# IoT_Pro_01.net
KiCad netlist of a schematic drawn in EAGLE
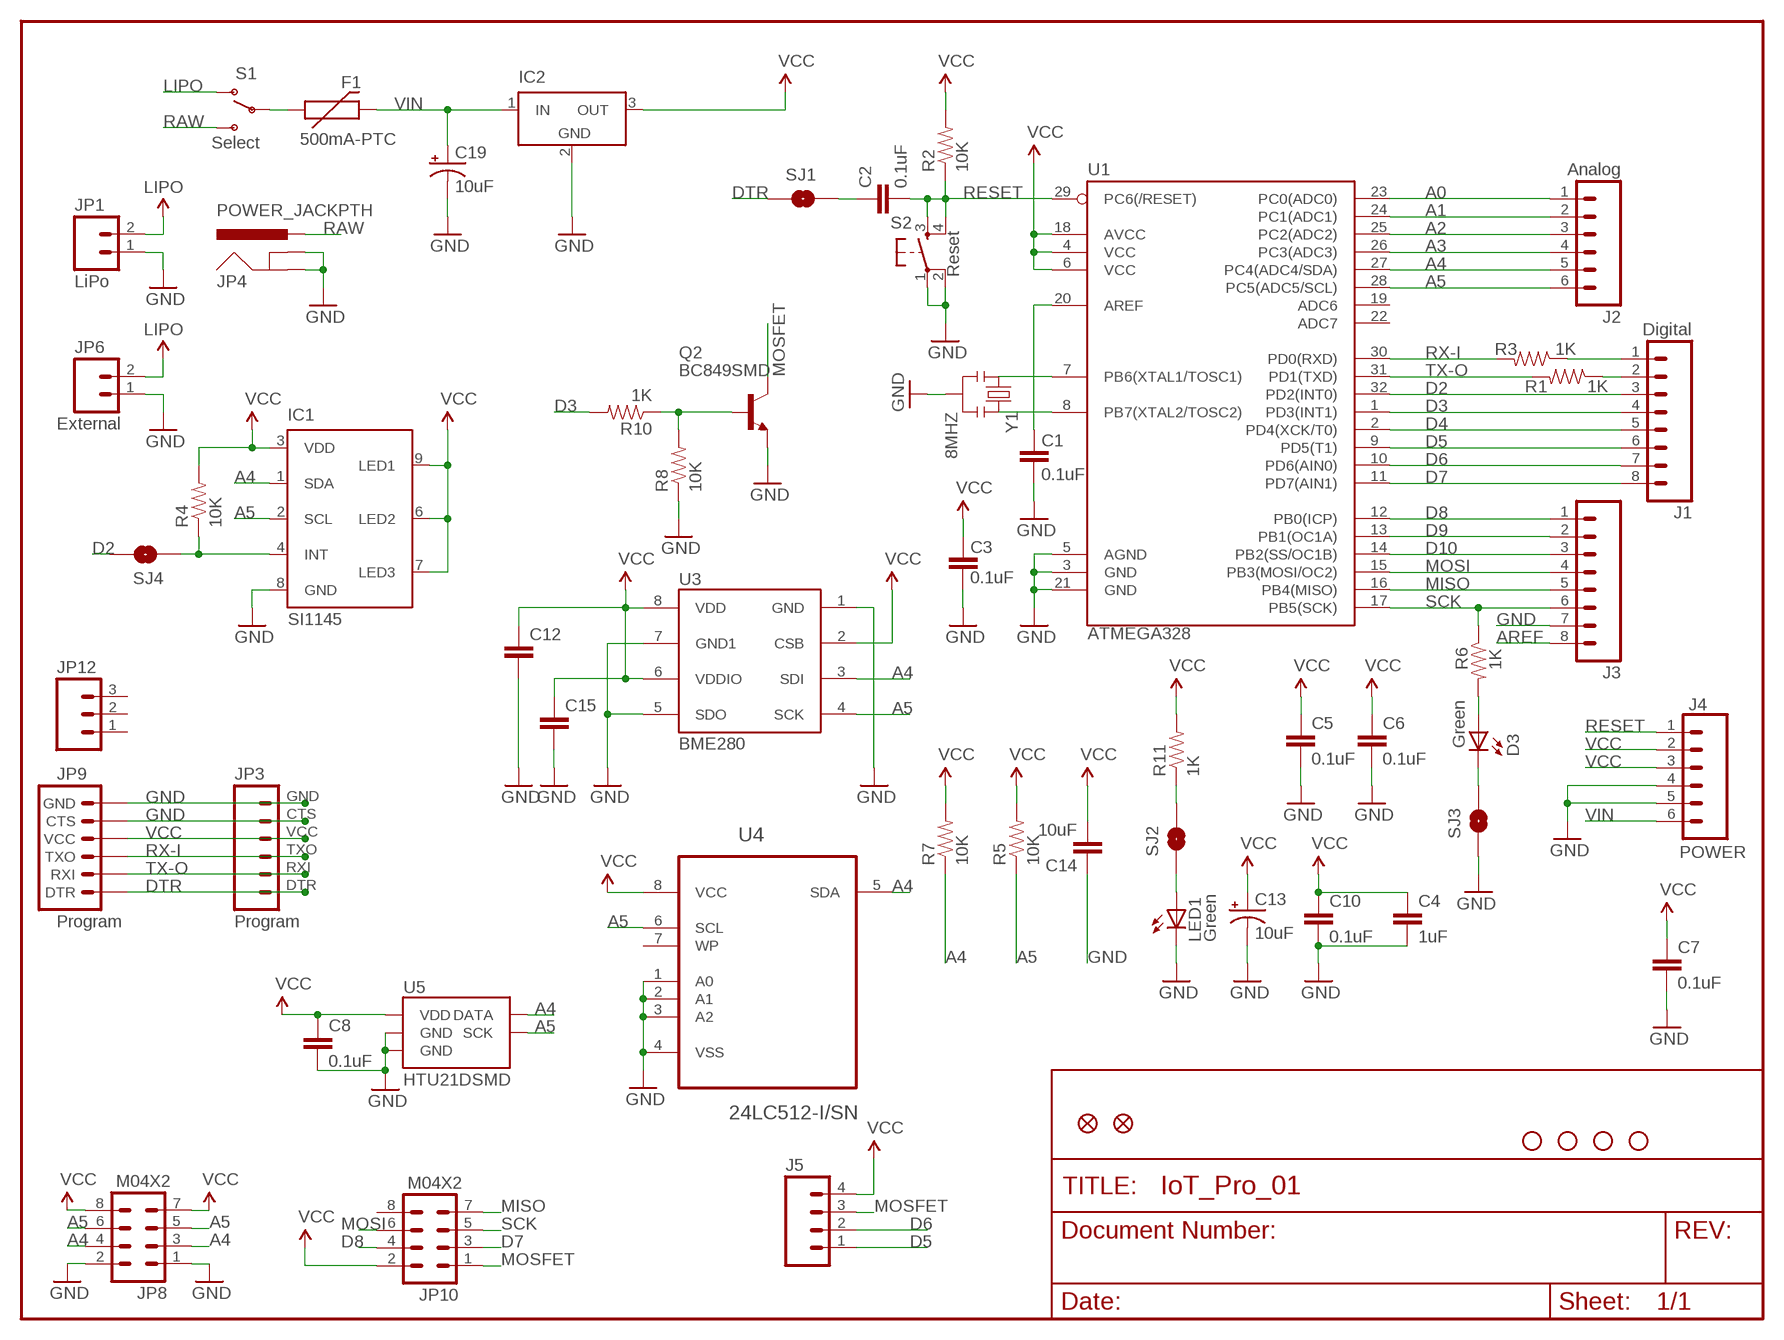
[diagram p0: schematic, sheet 1]

(export (version "E")
  (design (tool "Eeschema 10.0.6"))
  (components
    (comp (ref "C1")
      (value "0.1uF")
      (footprint "eagle-import:0805")
      (libsource (lib "eagle-import") (part "CAP0805"))
    )
    (comp (ref "C2")
      (value "0.1uF")
      (footprint "eagle-import:0805")
      (libsource (lib "eagle-import") (part "CAP0805"))
    )
    (comp (ref "C3")
      (value "0.1uF")
      (footprint "eagle-import:0805")
      (libsource (lib "eagle-import") (part "CAP0805"))
    )
    (comp (ref "C4")
      (value "1uF")
      (footprint "eagle-import:0805")
      (libsource (lib "eagle-import") (part "CAP0805"))
    )
    (comp (ref "C5")
      (value "0.1uF")
      (footprint "eagle-import:0805")
      (libsource (lib "eagle-import") (part "CAP0805"))
    )
    (comp (ref "C6")
      (value "0.1uF")
      (footprint "eagle-import:0805")
      (libsource (lib "eagle-import") (part "CAP0805"))
    )
    (comp (ref "C7")
      (value "0.1uF")
      (footprint "eagle-import:0805")
      (libsource (lib "eagle-import") (part "CAP0805"))
    )
    (comp (ref "C8")
      (value "0.1uF")
      (footprint "eagle-import:0805")
      (libsource (lib "eagle-import") (part "CAP0805"))
    )
    (comp (ref "C10")
      (value "0.1uF")
      (footprint "eagle-import:0805")
      (libsource (lib "eagle-import") (part "CAP0805"))
    )
    (comp (ref "C12")
      (value "CAP0805")
      (footprint "eagle-import:0805")
      (libsource (lib "eagle-import") (part "SparkFun-Capacitors_CAP0805"))
    )
    (comp (ref "C13")
      (value "10uF")
      (footprint "eagle-import:EIA3216")
      (libsource (lib "eagle-import") (part "CAP_POL1206"))
    )
    (comp (ref "C14")
      (value "10uF")
      (footprint "eagle-import:0805")
      (libsource (lib "eagle-import") (part "SparkFun-Capacitors_CAP0805"))
    )
    (comp (ref "C15")
      (value "CAP0805")
      (footprint "eagle-import:0805")
      (libsource (lib "eagle-import") (part "SparkFun-Capacitors_CAP0805"))
    )
    (comp (ref "C19")
      (value "10uF")
      (footprint "eagle-import:EIA3216")
      (libsource (lib "eagle-import") (part "CAP_POL1206"))
    )
    (comp (ref "D3")
      (value "Green")
      (footprint "eagle-import:PLCC2")
      (libsource (lib "eagle-import") (part "_T679-?-1E1F1LG"))
    )
    (comp (ref "F1")
      (value "500mA-PTC")
      (footprint "eagle-import:PTC-1206")
      (libsource (lib "eagle-import") (part "PTCSMD"))
    )
    (comp (ref "IC1")
      (value "SI1145")
      (footprint "eagle-import:QFN-10")
      (libsource (lib "eagle-import") (part "SI1145"))
    )
    (comp (ref "IC2")
      (value "LT1129CST5")
      (footprint "eagle-import:SOT223")
      (fields (field (name "MPN") "LT1129CST-5#PBF"))
      (libsource (lib "eagle-import") (part "LT1129CST5"))
    )
    (comp (ref "J1")
      (value "Digital")
      (footprint "eagle-import:1X08")
      (libsource (lib "eagle-import") (part "M081X08"))
    )
    (comp (ref "J2")
      (value "Analog")
      (footprint "eagle-import:1X06")
      (libsource (lib "eagle-import") (part "M06SIP"))
    )
    (comp (ref "J3")
      (value "M081X08")
      (footprint "eagle-import:1X08")
      (libsource (lib "eagle-import") (part "M081X08"))
    )
    (comp (ref "J4")
      (value "POWER")
      (footprint "eagle-import:1X06")
      (libsource (lib "eagle-import") (part "M06SIP"))
    )
    (comp (ref "J5")
      (value "M04PTH")
      (footprint "eagle-import:1X04")
      (libsource (lib "eagle-import") (part "M04PTH"))
    )
    (comp (ref "JP1")
      (value "LiPo")
      (footprint "eagle-import:MOLEX-1X2")
      (libsource (lib "eagle-import") (part "SparkFun-Connectors_M02POLAR"))
    )
    (comp (ref "JP2")
      (value "FIDUCIAL1X2.5")
      (footprint "eagle-import:FIDUCIAL-1X2.5")
      (libsource (lib "eagle-import") (part "FIDUCIAL1X2.5"))
    )
    (comp (ref "JP3")
      (value "Program")
      (footprint "eagle-import:1X06")
      (libsource (lib "eagle-import") (part "SparkFun-Connectors_M06SIP"))
    )
    (comp (ref "JP4")
      (value "POWER_JACKPTH")
      (footprint "eagle-import:POWER_JACK_PTH")
      (libsource (lib "eagle-import") (part "POWER_JACKPTH"))
    )
    (comp (ref "JP5")
      (value "FIDUCIAL1X2.5")
      (footprint "eagle-import:FIDUCIAL-1X2.5")
      (libsource (lib "eagle-import") (part "FIDUCIAL1X2.5"))
    )
    (comp (ref "JP6")
      (value "External")
      (footprint "eagle-import:1X02")
      (libsource (lib "eagle-import") (part "M02PTH"))
    )
    (comp (ref "JP8")
      (value "M04X2")
      (footprint "eagle-import:2X4")
      (libsource (lib "eagle-import") (part "M04X2"))
    )
    (comp (ref "JP9")
      (value "Program")
      (footprint "eagle-import:1X06-SMD")
      (libsource (lib "eagle-import") (part "ARDUINO_SERIAL_PROGRAMSMD"))
    )
    (comp (ref "JP10")
      (value "M04X2")
      (footprint "eagle-import:2X4")
      (libsource (lib "eagle-import") (part "M04X2"))
    )
    (comp (ref "JP12")
      (value "M03PTH")
      (footprint "eagle-import:1X03")
      (libsource (lib "eagle-import") (part "M03PTH"))
    )
    (comp (ref "LED1")
      (value "Green")
      (footprint "eagle-import:PLCC2")
      (libsource (lib "eagle-import") (part "_T679-?-1E1F1LG"))
    )
    (comp (ref "Q2")
      (value "BC849SMD")
      (footprint "eagle-import:SOT23-BEC")
      (libsource (lib "eagle-import") (part "BC849SMD"))
    )
    (comp (ref "R1")
      (value "1K")
      (footprint "eagle-import:0805")
      (libsource (lib "eagle-import") (part "RESISTOR0805-RES"))
    )
    (comp (ref "R2")
      (value "10K")
      (footprint "eagle-import:0805")
      (libsource (lib "eagle-import") (part "RESISTOR0805-RES"))
    )
    (comp (ref "R3")
      (value "1K")
      (footprint "eagle-import:0805")
      (libsource (lib "eagle-import") (part "RESISTOR0805-RES"))
    )
    (comp (ref "R4")
      (value "10K")
      (footprint "eagle-import:0805")
      (libsource (lib "eagle-import") (part "RESISTOR0805-RES"))
    )
    (comp (ref "R5")
      (value "10K")
      (footprint "eagle-import:0805")
      (libsource (lib "eagle-import") (part "RESISTOR0805-RES"))
    )
    (comp (ref "R6")
      (value "1K")
      (footprint "eagle-import:0805")
      (libsource (lib "eagle-import") (part "RESISTOR0805-RES"))
    )
    (comp (ref "R7")
      (value "10K")
      (footprint "eagle-import:0805")
      (libsource (lib "eagle-import") (part "RESISTOR0805-RES"))
    )
    (comp (ref "R8")
      (value "10K")
      (footprint "eagle-import:0805")
      (libsource (lib "eagle-import") (part "RESISTOR0805-RES"))
    )
    (comp (ref "R10")
      (value "1K")
      (footprint "eagle-import:0805")
      (libsource (lib "eagle-import") (part "RESISTOR0805-RES"))
    )
    (comp (ref "R11")
      (value "1K")
      (footprint "eagle-import:0805")
      (libsource (lib "eagle-import") (part "RESISTOR0805-RES"))
    )
    (comp (ref "S1")
      (value "Select")
      (footprint "eagle-import:SWITCH-SPST-SMD-A")
      (libsource (lib "eagle-import") (part "SWITCH-SPDT-SMD-A"))
    )
    (comp (ref "S2")
      (value "Reset")
      (footprint "eagle-import:TACTILE_SWITCH_SMD")
      (libsource (lib "eagle-import") (part "TAC_SWITCHSMD"))
    )
    (comp (ref "SJ1")
      (value "SOLDERJUMPERNC2")
      (footprint "eagle-import:SJ_2S-NOTRACE")
      (libsource (lib "eagle-import") (part "SOLDERJUMPERNC2"))
    )
    (comp (ref "SJ2")
      (value "SOLDERJUMPERNC2")
      (footprint "eagle-import:SJ_2S-NOTRACE")
      (libsource (lib "eagle-import") (part "SOLDERJUMPERNC2"))
    )
    (comp (ref "SJ3")
      (value "SOLDERJUMPERNC2")
      (footprint "eagle-import:SJ_2S-NOTRACE")
      (libsource (lib "eagle-import") (part "SOLDERJUMPERNC2"))
    )
    (comp (ref "SJ4")
      (value "SOLDERJUMPERNC2")
      (footprint "eagle-import:SJ_2S-NOTRACE")
      (libsource (lib "eagle-import") (part "SOLDERJUMPERNC2"))
    )
    (comp (ref "U$1")
      (value "STAND-OFFTIGHT")
      (footprint "eagle-import:STAND-OFF-TIGHT")
      (libsource (lib "eagle-import") (part "STAND-OFFTIGHT"))
    )
    (comp (ref "U$3")
      (value "STAND-OFFTIGHT")
      (footprint "eagle-import:STAND-OFF-TIGHT")
      (libsource (lib "eagle-import") (part "STAND-OFFTIGHT"))
    )
    (comp (ref "U$9")
      (value "STAND-OFFTIGHT")
      (footprint "eagle-import:STAND-OFF-TIGHT")
      (libsource (lib "eagle-import") (part "STAND-OFFTIGHT"))
    )
    (comp (ref "U$10")
      (value "STAND-OFFTIGHT")
      (footprint "eagle-import:STAND-OFF-TIGHT")
      (libsource (lib "eagle-import") (part "STAND-OFFTIGHT"))
    )
    (comp (ref "U1")
      (value "ATMEGA328")
      (footprint "eagle-import:TQFP32-08")
      (libsource (lib "eagle-import") (part "ATMEGA168"))
    )
    (comp (ref "U3")
      (value "BME280")
      (footprint "eagle-import:BME280")
      (libsource (lib "eagle-import") (part "BME280"))
    )
    (comp (ref "U4")
      (value "24LC512-I/SN")
      (footprint "eagle-import:SOIC127P600X175-8N")
      (libsource (lib "eagle-import") (part "24LC/SN512-I"))
    )
    (comp (ref "U5")
      (value "HTU21DSMD")
      (footprint "eagle-import:HTU21D")
      (libsource (lib "eagle-import") (part "HTU21DSMD"))
    )
    (comp (ref "Y1")
      (value "8MHZ")
      (footprint "eagle-import:RESONATOR-SMD")
      (libsource (lib "eagle-import") (part "RESONATOR8MHZ"))
    )
  )
  (nets
    (net (code "1") (name "/A0") (class "Default")
      (node (ref "J2") (pin "1") (pinfunction "1_1") (pintype "passive"))
      (node (ref "U1") (pin "23") (pinfunction "PC0(ADC0)_23") (pintype "bidirectional"))
    )
    (net (code "2") (name "/A1") (class "Default")
      (node (ref "J2") (pin "2") (pinfunction "2_2") (pintype "passive"))
      (node (ref "U1") (pin "24") (pinfunction "PC1(ADC1)_24") (pintype "bidirectional"))
    )
    (net (code "3") (name "/A2") (class "Default")
      (node (ref "J2") (pin "3") (pinfunction "3_3") (pintype "passive"))
      (node (ref "U1") (pin "25") (pinfunction "PC2(ADC2)_25") (pintype "bidirectional"))
    )
    (net (code "4") (name "/A3") (class "Default")
      (node (ref "J2") (pin "4") (pinfunction "4_4") (pintype "passive"))
      (node (ref "U1") (pin "26") (pinfunction "PC3(ADC3)_26") (pintype "bidirectional"))
    )
    (net (code "5") (name "/A4") (class "Default")
      (node (ref "IC1") (pin "1") (pinfunction "SDA_1") (pintype "bidirectional"))
      (node (ref "J2") (pin "5") (pinfunction "5_5") (pintype "passive"))
      (node (ref "JP8") (pin "3") (pinfunction "3_3") (pintype "passive"))
      (node (ref "JP8") (pin "4") (pinfunction "4_4") (pintype "passive"))
      (node (ref "R7") (pin "1") (pinfunction "1_1") (pintype "passive"))
      (node (ref "U1") (pin "27") (pinfunction "PC4(ADC4/SDA)_27") (pintype "bidirectional"))
      (node (ref "U3") (pin "3") (pinfunction "SDI_3") (pintype "power_in"))
      (node (ref "U4") (pin "5") (pinfunction "SDA_5") (pintype "bidirectional"))
      (node (ref "U5") (pin "DATA") (pinfunction "DATA_DATA") (pintype "bidirectional"))
    )
    (net (code "6") (name "/A5") (class "Default")
      (node (ref "IC1") (pin "2") (pinfunction "SCL_2") (pintype "input"))
      (node (ref "J2") (pin "6") (pinfunction "6_6") (pintype "passive"))
      (node (ref "JP8") (pin "5") (pinfunction "5_5") (pintype "passive"))
      (node (ref "JP8") (pin "6") (pinfunction "6_6") (pintype "passive"))
      (node (ref "R5") (pin "1") (pinfunction "1_1") (pintype "passive"))
      (node (ref "U1") (pin "28") (pinfunction "PC5(ADC5/SCL)_28") (pintype "bidirectional"))
      (node (ref "U3") (pin "4") (pinfunction "SCK_4") (pintype "power_in"))
      (node (ref "U4") (pin "6") (pinfunction "SCL_6") (pintype "input"))
      (node (ref "U5") (pin "SCK") (pinfunction "SCK_SCK") (pintype "input"))
    )
    (net (code "7") (name "/AREF") (class "Default")
      (node (ref "C1") (pin "2") (pinfunction "2_2") (pintype "passive"))
      (node (ref "J3") (pin "8") (pinfunction "8_8") (pintype "passive"))
      (node (ref "U1") (pin "20") (pinfunction "AREF_20") (pintype "bidirectional"))
    )
    (net (code "8") (name "/D2") (class "Default")
      (node (ref "J1") (pin "3") (pinfunction "3_3") (pintype "passive"))
      (node (ref "SJ4") (pin "2") (pinfunction "2_2") (pintype "passive"))
      (node (ref "U1") (pin "32") (pinfunction "PD2(INT0)_32") (pintype "bidirectional"))
    )
    (net (code "9") (name "/D3") (class "Default")
      (node (ref "J1") (pin "4") (pinfunction "4_4") (pintype "passive"))
      (node (ref "R10") (pin "2") (pinfunction "2_2") (pintype "passive"))
      (node (ref "U1") (pin "1") (pinfunction "PD3(INT1)_1") (pintype "bidirectional"))
    )
    (net (code "10") (name "/D4") (class "Default")
      (node (ref "J1") (pin "5") (pinfunction "5_5") (pintype "passive"))
      (node (ref "U1") (pin "2") (pinfunction "PD4(XCK/T0)_2") (pintype "bidirectional"))
    )
    (net (code "11") (name "/D5") (class "Default")
      (node (ref "J1") (pin "6") (pinfunction "6_6") (pintype "passive"))
      (node (ref "J5") (pin "1") (pinfunction "1_1") (pintype "passive"))
      (node (ref "U1") (pin "9") (pinfunction "PD5(T1)_9") (pintype "bidirectional"))
    )
    (net (code "12") (name "/D6") (class "Default")
      (node (ref "J1") (pin "7") (pinfunction "7_7") (pintype "passive"))
      (node (ref "J5") (pin "2") (pinfunction "2_2") (pintype "passive"))
      (node (ref "U1") (pin "10") (pinfunction "PD6(AIN0)_10") (pintype "bidirectional"))
    )
    (net (code "13") (name "/D7") (class "Default")
      (node (ref "J1") (pin "8") (pinfunction "8_8") (pintype "passive"))
      (node (ref "JP10") (pin "3") (pinfunction "3_3") (pintype "passive"))
      (node (ref "U1") (pin "11") (pinfunction "PD7(AIN1)_11") (pintype "bidirectional"))
    )
    (net (code "14") (name "/D8") (class "Default")
      (node (ref "J3") (pin "1") (pinfunction "1_1") (pintype "passive"))
      (node (ref "JP10") (pin "4") (pinfunction "4_4") (pintype "passive"))
      (node (ref "U1") (pin "12") (pinfunction "PB0(ICP)_12") (pintype "bidirectional"))
    )
    (net (code "15") (name "/D9") (class "Default")
      (node (ref "J3") (pin "2") (pinfunction "2_2") (pintype "passive"))
      (node (ref "U1") (pin "13") (pinfunction "PB1(OC1A)_13") (pintype "bidirectional"))
    )
    (net (code "16") (name "/D10") (class "Default")
      (node (ref "J3") (pin "3") (pinfunction "3_3") (pintype "passive"))
      (node (ref "U1") (pin "14") (pinfunction "PB2(SS/OC1B)_14") (pintype "bidirectional"))
    )
    (net (code "17") (name "/DTR") (class "Default")
      (node (ref "JP3") (pin "DTR") (pinfunction "1_DTR") (pintype "passive"))
      (node (ref "JP9") (pin "1") (pinfunction "DTR_1") (pintype "passive"))
      (node (ref "SJ1") (pin "1") (pinfunction "1_1") (pintype "passive"))
    )
    (net (code "18") (name "/MISO") (class "Default")
      (node (ref "J3") (pin "5") (pinfunction "5_5") (pintype "passive"))
      (node (ref "JP10") (pin "7") (pinfunction "7_7") (pintype "passive"))
      (node (ref "U1") (pin "16") (pinfunction "PB4(MISO)_16") (pintype "bidirectional"))
    )
    (net (code "19") (name "/MOSFET") (class "Default")
      (node (ref "J5") (pin "3") (pinfunction "3_3") (pintype "passive"))
      (node (ref "JP10") (pin "1") (pinfunction "1_1") (pintype "passive"))
      (node (ref "Q2") (pin "C") (pinfunction "C_C") (pintype "passive"))
    )
    (net (code "20") (name "/MOSI") (class "Default")
      (node (ref "J3") (pin "4") (pinfunction "4_4") (pintype "passive"))
      (node (ref "JP10") (pin "6") (pinfunction "6_6") (pintype "passive"))
      (node (ref "U1") (pin "15") (pinfunction "PB3(MOSI/OC2)_15") (pintype "bidirectional"))
    )
    (net (code "21") (name "/RAW") (class "Default")
      (node (ref "JP4") (pin "PWR") (pinfunction "PWR_PWR") (pintype "bidirectional"))
      (node (ref "S1") (pin "3") (pinfunction "S_3") (pintype "passive"))
    )
    (net (code "22") (name "/RESET") (class "Default")
      (node (ref "C2") (pin "2") (pinfunction "2_2") (pintype "passive"))
      (node (ref "J4") (pin "1") (pinfunction "1_1") (pintype "passive"))
      (node (ref "R2") (pin "1") (pinfunction "1_1") (pintype "passive"))
      (node (ref "S2") (pin "3") (pinfunction "3_3") (pintype "passive"))
      (node (ref "S2") (pin "4") (pinfunction "4_4") (pintype "passive"))
      (node (ref "U1") (pin "29") (pinfunction "PC6(/RESET)_29") (pintype "bidirectional"))
    )
    (net (code "23") (name "/RX-I") (class "Default")
      (node (ref "JP3") (pin "TXO") (pinfunction "3_TXO") (pintype "passive"))
      (node (ref "JP9") (pin "3") (pinfunction "TXO_3") (pintype "passive"))
      (node (ref "R3") (pin "2") (pinfunction "2_2") (pintype "passive"))
      (node (ref "U1") (pin "30") (pinfunction "PD0(RXD)_30") (pintype "bidirectional"))
    )
    (net (code "24") (name "/SCK") (class "Default")
      (node (ref "J3") (pin "6") (pinfunction "6_6") (pintype "passive"))
      (node (ref "JP10") (pin "5") (pinfunction "5_5") (pintype "passive"))
      (node (ref "R6") (pin "1") (pinfunction "1_1") (pintype "passive"))
      (node (ref "U1") (pin "17") (pinfunction "PB5(SCK)_17") (pintype "bidirectional"))
    )
    (net (code "25") (name "/TX-O") (class "Default")
      (node (ref "JP3") (pin "RXI") (pinfunction "2_RXI") (pintype "passive"))
      (node (ref "JP9") (pin "2") (pinfunction "RXI_2") (pintype "passive"))
      (node (ref "R1") (pin "2") (pinfunction "2_2") (pintype "passive"))
      (node (ref "U1") (pin "31") (pinfunction "PD1(TXD)_31") (pintype "bidirectional"))
    )
    (net (code "26") (name "/VIN") (class "Default")
      (node (ref "C19") (pin "A") (pinfunction "+_A") (pintype "passive"))
      (node (ref "F1") (pin "2") (pinfunction "2_2") (pintype "bidirectional"))
      (node (ref "IC2") (pin "1") (pinfunction "IN_1") (pintype "input"))
      (node (ref "J4") (pin "6") (pinfunction "6_6") (pintype "passive"))
    )
    (net (code "27") (name "GND") (class "Default")
      (node (ref "C1") (pin "1") (pinfunction "1_1") (pintype "passive"))
      (node (ref "C10") (pin "2") (pinfunction "2_2") (pintype "passive"))
      (node (ref "C12") (pin "2") (pinfunction "2_2") (pintype "passive"))
      (node (ref "C13") (pin "C") (pinfunction "-_C") (pintype "passive"))
      (node (ref "C14") (pin "1") (pinfunction "1_1") (pintype "passive"))
      (node (ref "C15") (pin "2") (pinfunction "2_2") (pintype "passive"))
      (node (ref "C19") (pin "C") (pinfunction "-_C") (pintype "passive"))
      (node (ref "C3") (pin "1") (pinfunction "1_1") (pintype "passive"))
      (node (ref "C4") (pin "2") (pinfunction "2_2") (pintype "passive"))
      (node (ref "C5") (pin "2") (pinfunction "2_2") (pintype "passive"))
      (node (ref "C6") (pin "2") (pinfunction "2_2") (pintype "passive"))
      (node (ref "C7") (pin "2") (pinfunction "2_2") (pintype "passive"))
      (node (ref "C8") (pin "2") (pinfunction "2_2") (pintype "passive"))
      (node (ref "IC1") (pin "8") (pinfunction "GND_8") (pintype "power_in"))
      (node (ref "IC2") (pin "2") (pinfunction "GND_2") (pintype "power_in"))
      (node (ref "J3") (pin "7") (pinfunction "7_7") (pintype "passive"))
      (node (ref "J4") (pin "4") (pinfunction "4_4") (pintype "passive"))
      (node (ref "J4") (pin "5") (pinfunction "5_5") (pintype "passive"))
      (node (ref "JP1") (pin "1") (pinfunction "1_1") (pintype "passive"))
      (node (ref "JP3") (pin "CTS") (pinfunction "5_CTS") (pintype "passive"))
      (node (ref "JP3") (pin "GND") (pinfunction "6_GND") (pintype "passive"))
      (node (ref "JP4") (pin "GND") (pinfunction "GND_GND") (pintype "bidirectional"))
      (node (ref "JP4") (pin "GNDBREAK") (pinfunction "GNDBREAK_GNDBREAK") (pintype "bidirectional"))
      (node (ref "JP6") (pin "1") (pinfunction "1_1") (pintype "passive"))
      (node (ref "JP8") (pin "1") (pinfunction "1_1") (pintype "passive"))
      (node (ref "JP8") (pin "2") (pinfunction "2_2") (pintype "passive"))
      (node (ref "JP9") (pin "5") (pinfunction "CTS_5") (pintype "passive"))
      (node (ref "JP9") (pin "6") (pinfunction "GND_6") (pintype "passive"))
      (node (ref "LED1") (pin "C") (pinfunction "C_C") (pintype "passive"))
      (node (ref "Q2") (pin "E") (pinfunction "E_E") (pintype "passive"))
      (node (ref "R8") (pin "1") (pinfunction "1_1") (pintype "passive"))
      (node (ref "S2") (pin "1") (pinfunction "1_1") (pintype "passive"))
      (node (ref "S2") (pin "2") (pinfunction "2_2") (pintype "passive"))
      (node (ref "SJ3") (pin "1") (pinfunction "1_1") (pintype "passive"))
      (node (ref "U1") (pin "21") (pinfunction "GND_21") (pintype "bidirectional"))
      (node (ref "U1") (pin "3") (pinfunction "GND_3") (pintype "bidirectional"))
      (node (ref "U1") (pin "5") (pinfunction "AGND_5") (pintype "bidirectional"))
      (node (ref "U3") (pin "1") (pinfunction "GND_1") (pintype "power_in"))
      (node (ref "U3") (pin "5") (pinfunction "SDO_5") (pintype "input"))
      (node (ref "U3") (pin "7") (pinfunction "GND1_7") (pintype "bidirectional"))
      (node (ref "U4") (pin "1") (pinfunction "A0_1") (pintype "input"))
      (node (ref "U4") (pin "2") (pinfunction "A1_2") (pintype "input"))
      (node (ref "U4") (pin "3") (pinfunction "A2_3") (pintype "input"))
      (node (ref "U4") (pin "4") (pinfunction "VSS_4") (pintype "power_in"))
      (node (ref "U5") (pin "7") (pinfunction "GND_7") (pintype "power_in"))
      (node (ref "U5") (pin "GND") (pinfunction "GND_GND") (pintype "power_in"))
      (node (ref "Y1") (pin "2") (pinfunction "2_2") (pintype "passive"))
    )
    (net (code "28") (name "LIPO") (class "Default")
      (node (ref "JP1") (pin "2") (pinfunction "2_2") (pintype "passive"))
      (node (ref "JP6") (pin "2") (pinfunction "2_2") (pintype "passive"))
      (node (ref "S1") (pin "1") (pinfunction "O_1") (pintype "passive"))
    )
    (net (code "29") (name "Net-(C2-Pad1)") (class "Default")
      (node (ref "C2") (pin "1") (pinfunction "1_1") (pintype "passive"))
      (node (ref "SJ1") (pin "2") (pinfunction "2_2") (pintype "passive"))
    )
    (net (code "30") (name "Net-(D3-PadA)") (class "Default")
      (node (ref "D3") (pin "A") (pinfunction "A_A") (pintype "passive"))
      (node (ref "R6") (pin "2") (pinfunction "2_2") (pintype "passive"))
    )
    (net (code "31") (name "Net-(D3-PadC)") (class "Default")
      (node (ref "D3") (pin "C") (pinfunction "C_C") (pintype "passive"))
      (node (ref "SJ3") (pin "2") (pinfunction "2_2") (pintype "passive"))
    )
    (net (code "32") (name "Net-(IC1-INT)") (class "Default")
      (node (ref "IC1") (pin "4") (pinfunction "INT_4") (pintype "open_collector"))
      (node (ref "R4") (pin "1") (pinfunction "1_1") (pintype "passive"))
      (node (ref "SJ4") (pin "1") (pinfunction "1_1") (pintype "passive"))
    )
    (net (code "33") (name "Net-(J1-Pad1)") (class "Default")
      (node (ref "J1") (pin "1") (pinfunction "1_1") (pintype "passive"))
      (node (ref "R3") (pin "1") (pinfunction "1_1") (pintype "passive"))
    )
    (net (code "34") (name "Net-(J1-Pad2)") (class "Default")
      (node (ref "J1") (pin "2") (pinfunction "2_2") (pintype "passive"))
      (node (ref "R1") (pin "1") (pinfunction "1_1") (pintype "passive"))
    )
    (net (code "35") (name "Net-(LED1-PadA)") (class "Default")
      (node (ref "LED1") (pin "A") (pinfunction "A_A") (pintype "passive"))
      (node (ref "SJ2") (pin "1") (pinfunction "1_1") (pintype "passive"))
    )
    (net (code "36") (name "Net-(Q2-PadB)") (class "Default")
      (node (ref "Q2") (pin "B") (pinfunction "B_B") (pintype "passive"))
      (node (ref "R10") (pin "1") (pinfunction "1_1") (pintype "passive"))
      (node (ref "R8") (pin "2") (pinfunction "2_2") (pintype "passive"))
    )
    (net (code "37") (name "Net-(R11-Pad1)") (class "Default")
      (node (ref "R11") (pin "1") (pinfunction "1_1") (pintype "passive"))
      (node (ref "SJ2") (pin "2") (pinfunction "2_2") (pintype "passive"))
    )
    (net (code "38") (name "Net-(S1-P)") (class "Default")
      (node (ref "F1") (pin "1") (pinfunction "1_1") (pintype "bidirectional"))
      (node (ref "S1") (pin "2") (pinfunction "P_2") (pintype "passive"))
    )
    (net (code "39") (name "Net-(U1-PB6(XTAL1{slash}TOSC1))") (class "Default")
      (node (ref "U1") (pin "7") (pinfunction "PB6(XTAL1/TOSC1)_7") (pintype "bidirectional"))
      (node (ref "Y1") (pin "1") (pinfunction "1_1") (pintype "passive"))
    )
    (net (code "40") (name "Net-(U1-PB7(XTAL2{slash}TOSC2))") (class "Default")
      (node (ref "U1") (pin "8") (pinfunction "PB7(XTAL2/TOSC2)_8") (pintype "bidirectional"))
      (node (ref "Y1") (pin "3") (pinfunction "3_3") (pintype "passive"))
    )
    (net (code "41") (name "VCC") (class "Default")
      (node (ref "C10") (pin "1") (pinfunction "1_1") (pintype "passive"))
      (node (ref "C12") (pin "1") (pinfunction "1_1") (pintype "passive"))
      (node (ref "C13") (pin "A") (pinfunction "+_A") (pintype "passive"))
      (node (ref "C14") (pin "2") (pinfunction "2_2") (pintype "passive"))
      (node (ref "C15") (pin "1") (pinfunction "1_1") (pintype "passive"))
      (node (ref "C3") (pin "2") (pinfunction "2_2") (pintype "passive"))
      (node (ref "C4") (pin "1") (pinfunction "1_1") (pintype "passive"))
      (node (ref "C5") (pin "1") (pinfunction "1_1") (pintype "passive"))
      (node (ref "C6") (pin "1") (pinfunction "1_1") (pintype "passive"))
      (node (ref "C7") (pin "1") (pinfunction "1_1") (pintype "passive"))
      (node (ref "C8") (pin "1") (pinfunction "1_1") (pintype "passive"))
      (node (ref "IC1") (pin "3") (pinfunction "VDD_3") (pintype "power_in"))
      (node (ref "IC1") (pin "6") (pinfunction "LED2_6") (pintype "output"))
      (node (ref "IC1") (pin "7") (pinfunction "LED3_7") (pintype "output"))
      (node (ref "IC1") (pin "9") (pinfunction "LED1_9") (pintype "output"))
      (node (ref "IC2") (pin "3") (pinfunction "OUT_3") (pintype "output"))
      (node (ref "J4") (pin "2") (pinfunction "2_2") (pintype "passive"))
      (node (ref "J4") (pin "3") (pinfunction "3_3") (pintype "passive"))
      (node (ref "J5") (pin "4") (pinfunction "4_4") (pintype "passive"))
      (node (ref "JP10") (pin "2") (pinfunction "2_2") (pintype "passive"))
      (node (ref "JP3") (pin "VCC") (pinfunction "4_VCC") (pintype "passive"))
      (node (ref "JP8") (pin "7") (pinfunction "7_7") (pintype "passive"))
      (node (ref "JP8") (pin "8") (pinfunction "8_8") (pintype "passive"))
      (node (ref "JP9") (pin "4") (pinfunction "VCC_4") (pintype "passive"))
      (node (ref "R11") (pin "2") (pinfunction "2_2") (pintype "passive"))
      (node (ref "R2") (pin "2") (pinfunction "2_2") (pintype "passive"))
      (node (ref "R4") (pin "2") (pinfunction "2_2") (pintype "passive"))
      (node (ref "R5") (pin "2") (pinfunction "2_2") (pintype "passive"))
      (node (ref "R7") (pin "2") (pinfunction "2_2") (pintype "passive"))
      (node (ref "U1") (pin "18") (pinfunction "AVCC_18") (pintype "bidirectional"))
      (node (ref "U1") (pin "4") (pinfunction "VCC_4") (pintype "bidirectional"))
      (node (ref "U1") (pin "6") (pinfunction "VCC_6") (pintype "bidirectional"))
      (node (ref "U3") (pin "2") (pinfunction "CSB_2") (pintype "power_in"))
      (node (ref "U3") (pin "6") (pinfunction "VDDIO_6") (pintype "input"))
      (node (ref "U3") (pin "8") (pinfunction "VDD_8") (pintype "bidirectional"))
      (node (ref "U4") (pin "8") (pinfunction "VCC_8") (pintype "power_in"))
      (node (ref "U5") (pin "VDD") (pinfunction "VDD_VDD") (pintype "power_in"))
    )
    (net (code "42") (name "unconnected-(JP10-Pad8)") (class "Default")
      (node (ref "JP10") (pin "8") (pinfunction "8_8") (pintype "passive"))
    )
    (net (code "43") (name "unconnected-(JP12-Pad1)") (class "Default")
      (node (ref "JP12") (pin "1") (pinfunction "1_1") (pintype "passive"))
    )
    (net (code "44") (name "unconnected-(JP12-Pad2)") (class "Default")
      (node (ref "JP12") (pin "2") (pinfunction "2_2") (pintype "passive"))
    )
    (net (code "45") (name "unconnected-(JP12-Pad3)") (class "Default")
      (node (ref "JP12") (pin "3") (pinfunction "3_3") (pintype "passive"))
    )
    (net (code "46") (name "unconnected-(U1-ADC6-Pad19)") (class "Default")
      (node (ref "U1") (pin "19") (pinfunction "ADC6_19") (pintype "bidirectional"))
    )
    (net (code "47") (name "unconnected-(U1-ADC7-Pad22)") (class "Default")
      (node (ref "U1") (pin "22") (pinfunction "ADC7_22") (pintype "bidirectional"))
    )
    (net (code "48") (name "unconnected-(U4-WP-Pad7)") (class "Default")
      (node (ref "U4") (pin "7") (pinfunction "WP_7") (pintype "input"))
    )
  )
)
